# SLAVE_HW.net
KiCad netlist of a schematic drawn in Altium Designer
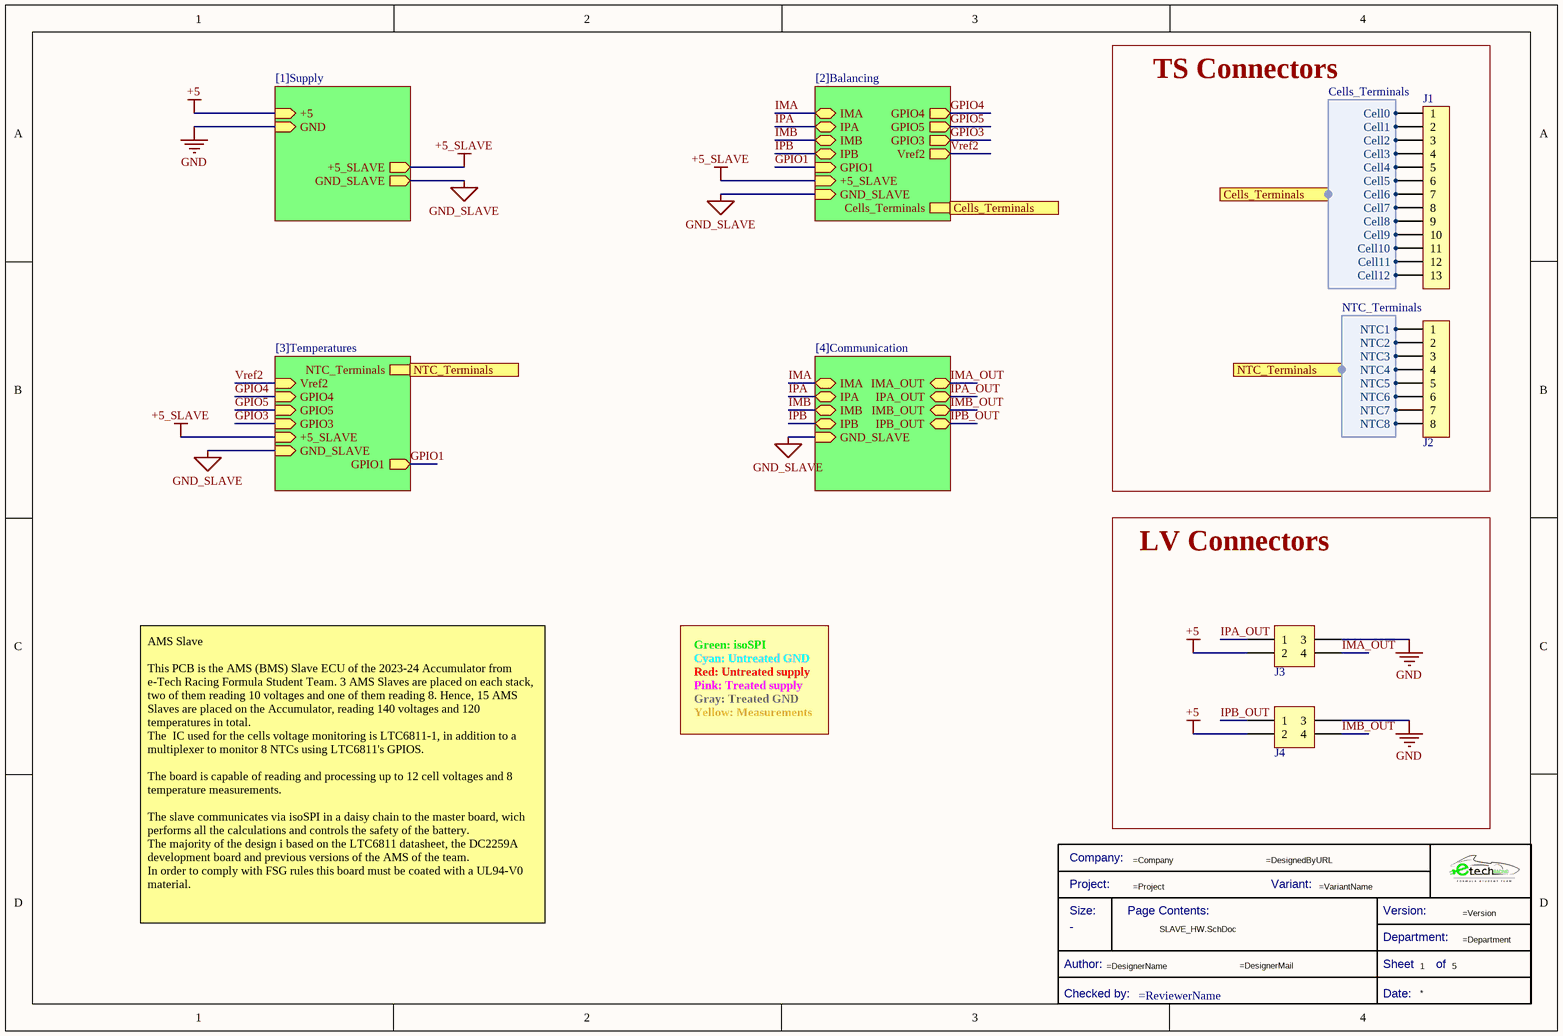
[diagram p0: SLAVE_HW.SchDoc]

(export (version "E")
  (design (tool "Eeschema 10.0.6"))
  (components
    (comp (ref "*")
      (value "Title Block_template")
      (description "Standard Title Block")
      (fields
        (field (name "SIZE") "-")
        (field (name ".CREATOR") "GP")
        (field (name ".PCBCHECK") "GP")
        (field (name ".SCHCHECK") "GP")
      )
      (libsource (lib "e-Tech_Racing") (part "Title Block_template"))
    )
    (comp (ref "J1")
      (value "61301311121")
      (footprint "J_Pinheader_1x13")
      (description "THT Vertical Pin Header WR-PHD, Pitch 2.54 mm, Single Row, 13 pins")
      (fields (field (name "MANUFACTURER") "Wurth Electronics"))
      (libsource (lib "Electromechanical") (part "J_Pinheader_1x13"))
    )
    (comp (ref "J2")
      (value "61301211121")
      (footprint "J_Pinheader_1x8")
      (description "THT Vertical Pin Header WR-PHD, Pitch 2.54 mm, Single Row, 12 pins")
      (libsource (lib "Electromechanical") (part "J_Pinheader_1x8"))
    )
    (comp (ref "J3")
      (value "J_NanoFit_2x2")
      (footprint "J_NanoFit_2x2_v")
      (description "Conn Nano-Fit Power HDR 4 POS 2.5mm Solder ST Through Hole 4 Terminal Single Port Tray")
      (libsource (lib "Electromechanical") (part "J_NanoFit_2x2"))
    )
    (comp (ref "J4")
      (value "J_NanoFit_2x2")
      (footprint "J_NanoFit_2x2_v")
      (description "Conn Nano-Fit Power HDR 4 POS 2.5mm Solder ST Through Hole 4 Terminal Single Port Tray")
      (libsource (lib "Electromechanical") (part "J_NanoFit_2x2"))
    )
  )
  (nets
    (net (code "3") (name "+5") (class "Default")
      (node (ref "J3") (pin "2") (pinfunction "2_2") (pintype "passive"))
      (node (ref "J4") (pin "2") (pinfunction "2_2") (pintype "passive"))
    )
    (net (code "5") (name "/Cell0") (class "Default")
      (node (ref "J1") (pin "1") (pinfunction "1_1") (pintype "passive"))
    )
    (net (code "6") (name "/Cell1") (class "Default")
      (node (ref "J1") (pin "2") (pinfunction "2_2") (pintype "passive"))
    )
    (net (code "7") (name "/Cell2") (class "Default")
      (node (ref "J1") (pin "3") (pinfunction "3_3") (pintype "passive"))
    )
    (net (code "8") (name "/Cell3") (class "Default")
      (node (ref "J1") (pin "4") (pinfunction "4_4") (pintype "passive"))
    )
    (net (code "9") (name "/Cell4") (class "Default")
      (node (ref "J1") (pin "5") (pinfunction "5_5") (pintype "passive"))
    )
    (net (code "10") (name "/Cell5") (class "Default")
      (node (ref "J1") (pin "6") (pinfunction "6_6") (pintype "passive"))
    )
    (net (code "11") (name "/Cell6") (class "Default")
      (node (ref "J1") (pin "7") (pinfunction "7_7") (pintype "passive"))
    )
    (net (code "12") (name "/Cell7") (class "Default")
      (node (ref "J1") (pin "8") (pinfunction "8_8") (pintype "passive"))
    )
    (net (code "13") (name "/Cell8") (class "Default")
      (node (ref "J1") (pin "9") (pinfunction "9_9") (pintype "passive"))
    )
    (net (code "14") (name "/Cell9") (class "Default")
      (node (ref "J1") (pin "10") (pinfunction "10_10") (pintype "passive"))
    )
    (net (code "15") (name "/Cell10") (class "Default")
      (node (ref "J1") (pin "11") (pinfunction "11_11") (pintype "passive"))
    )
    (net (code "16") (name "/Cell11") (class "Default")
      (node (ref "J1") (pin "12") (pinfunction "12_12") (pintype "passive"))
    )
    (net (code "17") (name "/Cell12") (class "Default")
      (node (ref "J1") (pin "13") (pinfunction "13_13") (pintype "passive"))
    )
    (net (code "23") (name "/IMA_OUT") (class "Default")
      (node (ref "J3") (pin "4") (pinfunction "4_4") (pintype "passive"))
    )
    (net (code "25") (name "/IMB_OUT") (class "Default")
      (node (ref "J4") (pin "4") (pinfunction "4_4") (pintype "passive"))
    )
    (net (code "27") (name "/IPA_OUT") (class "Default")
      (node (ref "J3") (pin "1") (pinfunction "1_1") (pintype "passive"))
    )
    (net (code "29") (name "/IPB_OUT") (class "Default")
      (node (ref "J4") (pin "1") (pinfunction "1_1") (pintype "passive"))
    )
    (net (code "30") (name "/NTC1") (class "Default")
      (node (ref "J2") (pin "1") (pinfunction "1_1") (pintype "passive"))
    )
    (net (code "31") (name "/NTC2") (class "Default")
      (node (ref "J2") (pin "2") (pinfunction "2_2") (pintype "passive"))
    )
    (net (code "32") (name "/NTC3") (class "Default")
      (node (ref "J2") (pin "3") (pinfunction "3_3") (pintype "passive"))
    )
    (net (code "33") (name "/NTC4") (class "Default")
      (node (ref "J2") (pin "4") (pinfunction "4_4") (pintype "passive"))
    )
    (net (code "34") (name "/NTC5") (class "Default")
      (node (ref "J2") (pin "5") (pinfunction "5_5") (pintype "passive"))
    )
    (net (code "35") (name "/NTC6") (class "Default")
      (node (ref "J2") (pin "6") (pinfunction "6_6") (pintype "passive"))
    )
    (net (code "36") (name "/NTC7") (class "Default")
      (node (ref "J2") (pin "7") (pinfunction "7_7") (pintype "passive"))
    )
    (net (code "37") (name "/NTC8") (class "Default")
      (node (ref "J2") (pin "8") (pinfunction "8_8") (pintype "passive"))
    )
    (net (code "41") (name "GND") (class "Default")
      (node (ref "J3") (pin "3") (pinfunction "3_3") (pintype "passive"))
      (node (ref "J4") (pin "3") (pinfunction "3_3") (pintype "passive"))
    )
  )
)
